# FiltreFSK_TI_LM386.net
KiCad netlist of a schematic drawn in EAGLE
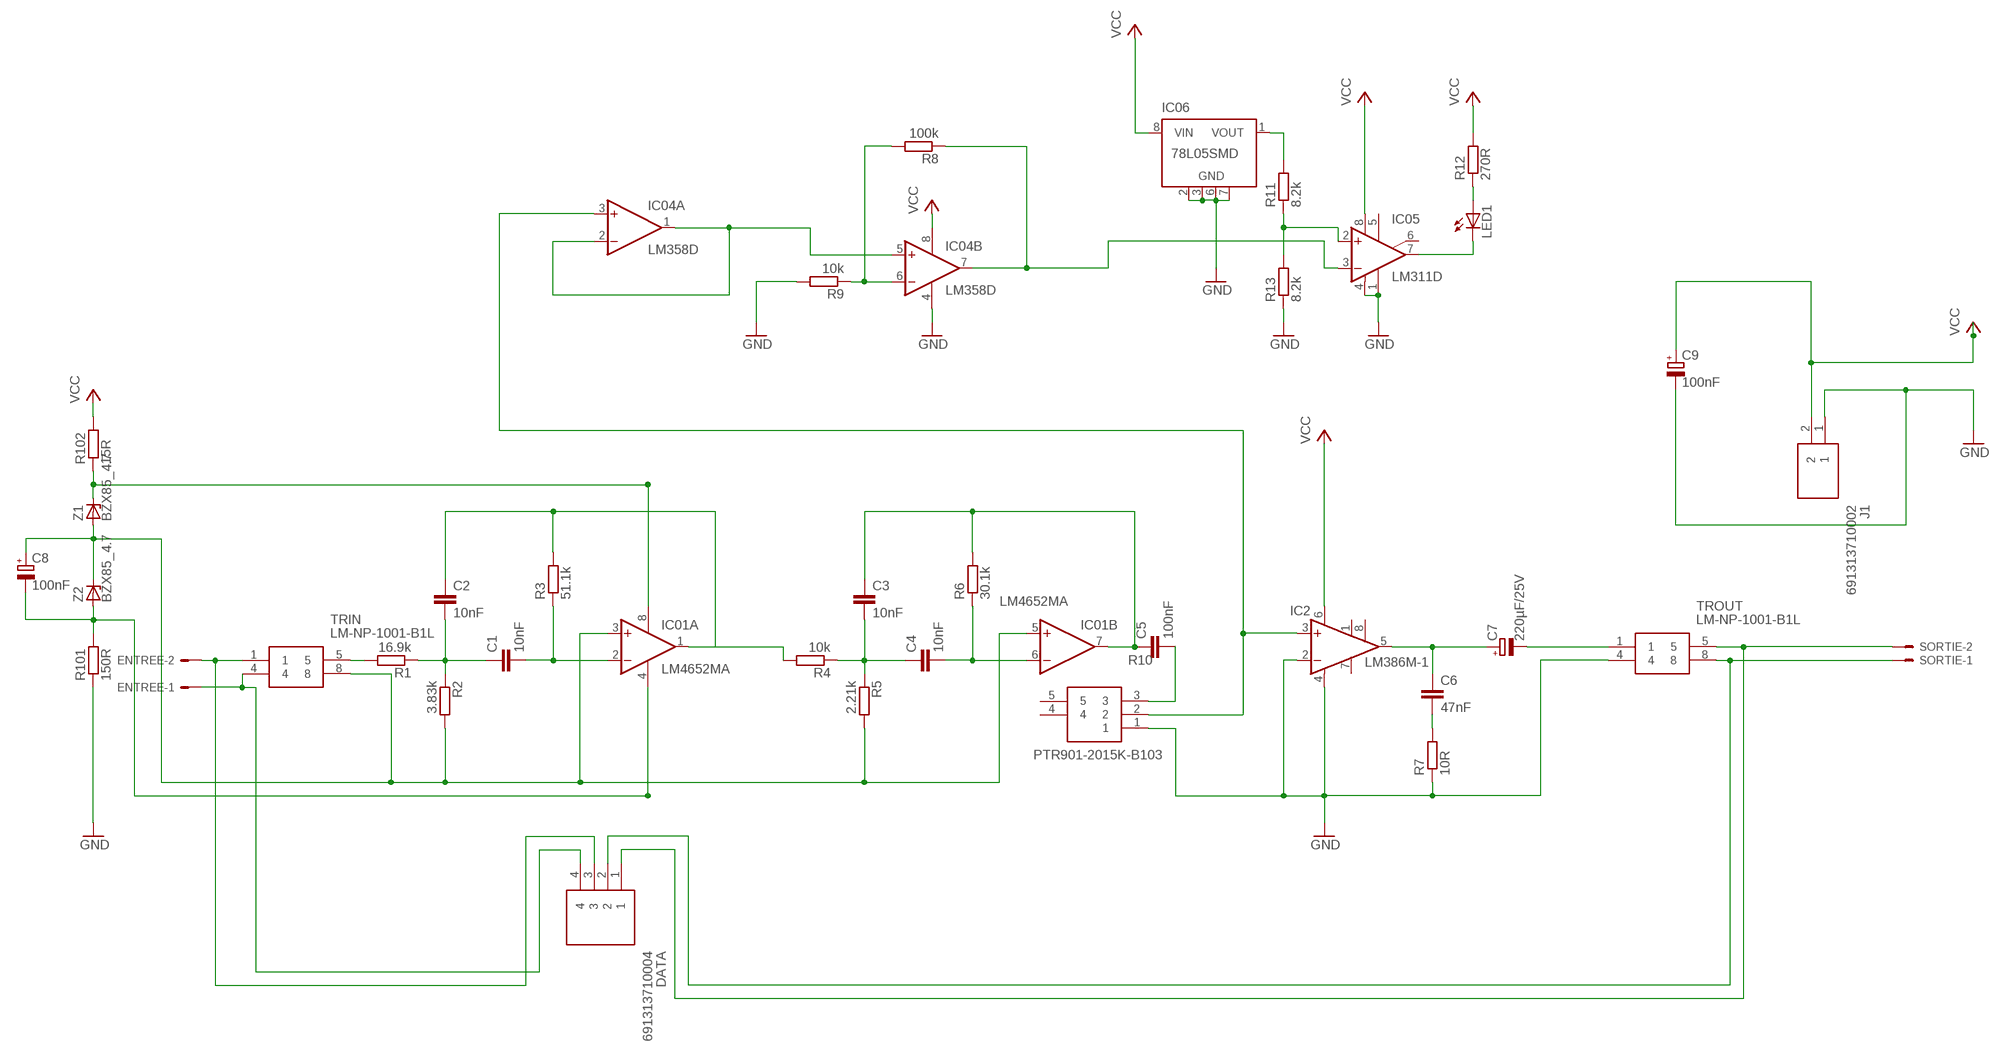
[diagram p0: schematic, sheet 1]

(export (version "E")
  (design (tool "Eeschema 10.0.6"))
  (components
    (comp (ref "C1")
      (value "10nF")
      (footprint "eagle-import:C1206")
      (libsource (lib "eagle-import") (part "C-EUC1206"))
    )
    (comp (ref "C2")
      (value "10nF")
      (footprint "eagle-import:C1206")
      (libsource (lib "eagle-import") (part "C-EUC1206"))
    )
    (comp (ref "C3")
      (value "10nF")
      (footprint "eagle-import:C1206")
      (libsource (lib "eagle-import") (part "C-EUC1206"))
    )
    (comp (ref "C4")
      (value "10nF")
      (footprint "eagle-import:C1206")
      (libsource (lib "eagle-import") (part "C-EUC1206"))
    )
    (comp (ref "C5")
      (value "100nF")
      (footprint "eagle-import:C1206")
      (libsource (lib "eagle-import") (part "C-EUC1206"))
    )
    (comp (ref "C6")
      (value "47nF")
      (footprint "eagle-import:C1206")
      (libsource (lib "eagle-import") (part "C-EUC1206"))
    )
    (comp (ref "C7")
      (value "220µF/25V")
      (footprint "eagle-import:E3,5-8")
      (libsource (lib "eagle-import") (part "CPOL-EUE3.5-8"))
    )
    (comp (ref "C8")
      (value "100nF")
      (footprint "eagle-import:E5-10,5")
      (libsource (lib "eagle-import") (part "CPOL-EUE5-10.5"))
    )
    (comp (ref "C9")
      (value "100nF")
      (footprint "eagle-import:E5-10,5")
      (libsource (lib "eagle-import") (part "CPOL-EUE5-10.5"))
    )
    (comp (ref "DATA")
      (value "691313710004")
      (footprint "eagle-import:SHDR4W140P0X500_1X4_2200X1200X")
      (fields
        (field (name "MOUSER_PART_NUMBER") "710-691313710004")
        (field (name "RS_PART_NUMBER") "8246576")
      )
      (libsource (lib "eagle-import") (part "691313710004"))
    )
    (comp (ref "ENTREE")
      (value "KK-156-2")
      (footprint "eagle-import:KK-156-2")
      (libsource (lib "eagle-import") (part "KK-156-2"))
    )
    (comp (ref "IC01")
      (value "LM4652MA")
      (footprint "eagle-import:SO08")
      (libsource (lib "eagle-import") (part "LM358D"))
    )
    (comp (ref "IC2")
      (value "LM386M-1")
      (footprint "eagle-import:SO08")
      (libsource (lib "eagle-import") (part "LM386?-M1"))
    )
    (comp (ref "IC04")
      (value "LM358D")
      (footprint "eagle-import:SO08")
      (libsource (lib "eagle-import") (part "LM358D"))
    )
    (comp (ref "IC05")
      (value "LM311D")
      (footprint "eagle-import:SO08")
      (libsource (lib "eagle-import") (part "LM311D"))
    )
    (comp (ref "IC06")
      (value "78L05SMD")
      (footprint "eagle-import:SO08")
      (libsource (lib "eagle-import") (part "78LSMD05"))
    )
    (comp (ref "J1")
      (value "691313710002")
      (footprint "eagle-import:691313710002")
      (fields (field (name "MOUSER_PART_NUMBER") "710-691313710002"))
      (libsource (lib "eagle-import") (part "691313710002"))
    )
    (comp (ref "LED1")
      (value "LED5MM")
      (footprint "eagle-import:LED5MM")
      (libsource (lib "eagle-import") (part "LED5MM"))
    )
    (comp (ref "R1")
      (value "16.9k")
      (footprint "eagle-import:R1206")
      (libsource (lib "eagle-import") (part "R-EU_R1206"))
    )
    (comp (ref "R2")
      (value "3.83k")
      (footprint "eagle-import:R1206")
      (libsource (lib "eagle-import") (part "R-EU_R1206"))
    )
    (comp (ref "R3")
      (value "51.1k")
      (footprint "eagle-import:R1206")
      (libsource (lib "eagle-import") (part "R-EU_R1206"))
    )
    (comp (ref "R4")
      (value "10k")
      (footprint "eagle-import:R1206")
      (libsource (lib "eagle-import") (part "R-EU_R1206"))
    )
    (comp (ref "R5")
      (value "2.21k")
      (footprint "eagle-import:R1206")
      (libsource (lib "eagle-import") (part "R-EU_R1206"))
    )
    (comp (ref "R6")
      (value "30.1k")
      (footprint "eagle-import:R1206")
      (libsource (lib "eagle-import") (part "R-EU_R1206"))
    )
    (comp (ref "R7")
      (value "10R")
      (footprint "eagle-import:R1206")
      (libsource (lib "eagle-import") (part "R-EU_R1206"))
    )
    (comp (ref "R8")
      (value "100k")
      (footprint "eagle-import:R1206")
      (libsource (lib "eagle-import") (part "R-EU_R1206"))
    )
    (comp (ref "R9")
      (value "10k")
      (footprint "eagle-import:R1206")
      (libsource (lib "eagle-import") (part "R-EU_R1206"))
    )
    (comp (ref "R10")
      (value "PTR901-2015K-B103")
      (footprint "eagle-import:PTR9012015KB103")
      (fields
        (field (name "MOUSER_PART_NUMBER") "652-PTR901-2015KB103")
        (field (name "RS_PART_NUMBER") "8275003P")
      )
      (libsource (lib "eagle-import") (part "PTR901-2015K-B103"))
    )
    (comp (ref "R11")
      (value "8.2k")
      (footprint "eagle-import:R1210")
      (libsource (lib "eagle-import") (part "R-EU_R1210"))
    )
    (comp (ref "R12")
      (value "270R")
      (footprint "eagle-import:R1206")
      (libsource (lib "eagle-import") (part "R-EU_R1206"))
    )
    (comp (ref "R13")
      (value "8.2k")
      (footprint "eagle-import:R1210")
      (libsource (lib "eagle-import") (part "R-EU_R1210"))
    )
    (comp (ref "R101")
      (value "150R")
      (footprint "eagle-import:0207_10")
      (libsource (lib "eagle-import") (part "R-EU_0207/10"))
    )
    (comp (ref "R102")
      (value "15R")
      (footprint "eagle-import:0207_10")
      (libsource (lib "eagle-import") (part "R-EU_0207/10"))
    )
    (comp (ref "SORTIE")
      (value "KK-156-2")
      (footprint "eagle-import:KK-156-2")
      (libsource (lib "eagle-import") (part "KK-156-2"))
    )
    (comp (ref "TRIN")
      (value "LM-NP-1001-B1L")
      (footprint "eagle-import:LMNP1001B1L")
      (fields
        (field (name "MOUSER_PART_NUMBER") "652-LM-NP-1001-B1L")
        (field (name "RS_PART_NUMBER") "1740620")
      )
      (libsource (lib "eagle-import") (part "LM-NP-1001-B1L"))
    )
    (comp (ref "TROUT")
      (value "LM-NP-1001-B1L")
      (footprint "eagle-import:LMNP1001B1L")
      (fields
        (field (name "MOUSER_PART_NUMBER") "652-LM-NP-1001-B1L")
        (field (name "RS_PART_NUMBER") "1740620")
      )
      (libsource (lib "eagle-import") (part "LM-NP-1001-B1L"))
    )
    (comp (ref "Z1")
      (value "BZX85_4.7")
      (footprint "eagle-import:DO41Z10")
      (libsource (lib "eagle-import") (part "BZX85"))
    )
    (comp (ref "Z2")
      (value "BZX85_4.7")
      (footprint "eagle-import:DO41Z10")
      (libsource (lib "eagle-import") (part "BZX85"))
    )
  )
  (nets
    (net (code "1") (name "GND") (class "Default")
      (node (ref "C9") (pin "-") (pinfunction "-_-") (pintype "passive"))
      (node (ref "IC04") (pin "4") (pinfunction "V-_4") (pintype "power_in"))
      (node (ref "IC05") (pin "1") (pinfunction "GND_1") (pintype "passive"))
      (node (ref "IC05") (pin "4") (pinfunction "V-_4") (pintype "power_in"))
      (node (ref "IC06") (pin "2") (pinfunction "GND_2") (pintype "power_in"))
      (node (ref "IC06") (pin "3") (pinfunction "GND_3") (pintype "power_in"))
      (node (ref "IC06") (pin "6") (pinfunction "GND_6") (pintype "power_in"))
      (node (ref "IC06") (pin "7") (pinfunction "GND_7") (pintype "power_in"))
      (node (ref "IC2") (pin "2") (pinfunction "-IN_2") (pintype "input"))
      (node (ref "IC2") (pin "4") (pinfunction "GND_4") (pintype "power_in"))
      (node (ref "J1") (pin "1") (pinfunction "1_1") (pintype "bidirectional"))
      (node (ref "R10") (pin "1") (pinfunction "1_1") (pintype "bidirectional"))
      (node (ref "R101") (pin "1") (pinfunction "1_1") (pintype "passive"))
      (node (ref "R13") (pin "1") (pinfunction "1_1") (pintype "passive"))
      (node (ref "R7") (pin "1") (pinfunction "1_1") (pintype "passive"))
      (node (ref "R9") (pin "2") (pinfunction "2_2") (pintype "passive"))
      (node (ref "TROUT") (pin "4") (pinfunction "4_4") (pintype "bidirectional"))
    )
    (net (code "2") (name "Net-(C1-Pad1)") (class "Default")
      (node (ref "C1") (pin "1") (pinfunction "1_1") (pintype "passive"))
      (node (ref "C2") (pin "2") (pinfunction "2_2") (pintype "passive"))
      (node (ref "R1") (pin "1") (pinfunction "1_1") (pintype "passive"))
      (node (ref "R2") (pin "1") (pinfunction "1_1") (pintype "passive"))
    )
    (net (code "3") (name "Net-(C3-Pad2)") (class "Default")
      (node (ref "C3") (pin "2") (pinfunction "2_2") (pintype "passive"))
      (node (ref "C4") (pin "1") (pinfunction "1_1") (pintype "passive"))
      (node (ref "R4") (pin "1") (pinfunction "1_1") (pintype "passive"))
      (node (ref "R5") (pin "1") (pinfunction "1_1") (pintype "passive"))
    )
    (net (code "4") (name "Net-(C5-Pad2)") (class "Default")
      (node (ref "C5") (pin "2") (pinfunction "2_2") (pintype "passive"))
      (node (ref "R10") (pin "3") (pinfunction "3_3") (pintype "bidirectional"))
    )
    (net (code "5") (name "Net-(C6-Pad2)") (class "Default")
      (node (ref "C6") (pin "2") (pinfunction "2_2") (pintype "passive"))
      (node (ref "R7") (pin "2") (pinfunction "2_2") (pintype "passive"))
    )
    (net (code "6") (name "Net-(C7-Pad-)") (class "Default")
      (node (ref "C7") (pin "-") (pinfunction "-_-") (pintype "passive"))
      (node (ref "TROUT") (pin "1") (pinfunction "1_1") (pintype "bidirectional"))
    )
    (net (code "7") (name "Net-(ENTREEA-S)") (class "Default")
      (node (ref "DATA") (pin "4") (pinfunction "4_4") (pintype "bidirectional"))
      (node (ref "ENTREE") (pin "1") (pinfunction "S_1") (pintype "passive"))
      (node (ref "TRIN") (pin "4") (pinfunction "4_4") (pintype "bidirectional"))
    )
    (net (code "8") (name "Net-(ENTREEB-S)") (class "Default")
      (node (ref "DATA") (pin "3") (pinfunction "3_3") (pintype "bidirectional"))
      (node (ref "ENTREE") (pin "2") (pinfunction "S_2") (pintype "passive"))
      (node (ref "TRIN") (pin "1") (pinfunction "1_1") (pintype "bidirectional"))
    )
    (net (code "9") (name "Net-(IC01A-+IN)") (class "Default")
      (node (ref "C8") (pin "+") (pinfunction "+_+") (pintype "passive"))
      (node (ref "IC01") (pin "3") (pinfunction "+IN_3") (pintype "input"))
      (node (ref "IC01") (pin "5") (pinfunction "+IN_5") (pintype "input"))
      (node (ref "R2") (pin "2") (pinfunction "2_2") (pintype "passive"))
      (node (ref "R5") (pin "2") (pinfunction "2_2") (pintype "passive"))
      (node (ref "TRIN") (pin "8") (pinfunction "8_8") (pintype "bidirectional"))
      (node (ref "Z1") (pin "A") (pinfunction "A_A") (pintype "passive"))
      (node (ref "Z2") (pin "C") (pinfunction "C_C") (pintype "passive"))
    )
    (net (code "10") (name "Net-(IC01A--IN)") (class "Default")
      (node (ref "C1") (pin "2") (pinfunction "2_2") (pintype "passive"))
      (node (ref "IC01") (pin "2") (pinfunction "-IN_2") (pintype "input"))
      (node (ref "R3") (pin "1") (pinfunction "1_1") (pintype "passive"))
    )
    (net (code "11") (name "Net-(IC01A-OUT)") (class "Default")
      (node (ref "C2") (pin "1") (pinfunction "1_1") (pintype "passive"))
      (node (ref "IC01") (pin "1") (pinfunction "OUT_1") (pintype "output"))
      (node (ref "R3") (pin "2") (pinfunction "2_2") (pintype "passive"))
      (node (ref "R4") (pin "2") (pinfunction "2_2") (pintype "passive"))
    )
    (net (code "12") (name "Net-(IC01B--IN)") (class "Default")
      (node (ref "C4") (pin "2") (pinfunction "2_2") (pintype "passive"))
      (node (ref "IC01") (pin "6") (pinfunction "-IN_6") (pintype "input"))
      (node (ref "R6") (pin "1") (pinfunction "1_1") (pintype "passive"))
    )
    (net (code "13") (name "Net-(IC01B-OUT)") (class "Default")
      (node (ref "C3") (pin "1") (pinfunction "1_1") (pintype "passive"))
      (node (ref "C5") (pin "1") (pinfunction "1_1") (pintype "passive"))
      (node (ref "IC01") (pin "7") (pinfunction "OUT_7") (pintype "output"))
      (node (ref "R6") (pin "2") (pinfunction "2_2") (pintype "passive"))
    )
    (net (code "14") (name "Net-(IC01C-V+)") (class "Default")
      (node (ref "IC01") (pin "8") (pinfunction "V+_8") (pintype "power_in"))
      (node (ref "R102") (pin "1") (pinfunction "1_1") (pintype "passive"))
      (node (ref "Z1") (pin "C") (pinfunction "C_C") (pintype "passive"))
    )
    (net (code "15") (name "Net-(IC01C-V-)") (class "Default")
      (node (ref "C8") (pin "-") (pinfunction "-_-") (pintype "passive"))
      (node (ref "IC01") (pin "4") (pinfunction "V-_4") (pintype "power_in"))
      (node (ref "R101") (pin "2") (pinfunction "2_2") (pintype "passive"))
      (node (ref "Z2") (pin "A") (pinfunction "A_A") (pintype "passive"))
    )
    (net (code "16") (name "Net-(IC2-OUT)") (class "Default")
      (node (ref "C6") (pin "1") (pinfunction "1_1") (pintype "passive"))
      (node (ref "C7") (pin "+") (pinfunction "+_+") (pintype "passive"))
      (node (ref "IC2") (pin "5") (pinfunction "OUT_5") (pintype "output"))
    )
    (net (code "17") (name "Net-(IC04A-+IN)") (class "Default")
      (node (ref "IC04") (pin "3") (pinfunction "+IN_3") (pintype "input"))
      (node (ref "IC2") (pin "3") (pinfunction "+IN_3") (pintype "input"))
      (node (ref "R10") (pin "2") (pinfunction "2_2") (pintype "bidirectional"))
    )
    (net (code "18") (name "Net-(IC04A--IN)") (class "Default")
      (node (ref "IC04") (pin "1") (pinfunction "OUT_1") (pintype "output"))
      (node (ref "IC04") (pin "2") (pinfunction "-IN_2") (pintype "input"))
      (node (ref "IC04") (pin "5") (pinfunction "+IN_5") (pintype "input"))
    )
    (net (code "19") (name "Net-(IC04B--IN)") (class "Default")
      (node (ref "IC04") (pin "6") (pinfunction "-IN_6") (pintype "input"))
      (node (ref "R8") (pin "2") (pinfunction "2_2") (pintype "passive"))
      (node (ref "R9") (pin "1") (pinfunction "1_1") (pintype "passive"))
    )
    (net (code "20") (name "Net-(IC04B-OUT)") (class "Default")
      (node (ref "IC04") (pin "7") (pinfunction "OUT_7") (pintype "output"))
      (node (ref "IC05") (pin "3") (pinfunction "-IN_3") (pintype "input"))
      (node (ref "R8") (pin "1") (pinfunction "1_1") (pintype "passive"))
    )
    (net (code "21") (name "Net-(IC05-+IN)") (class "Default")
      (node (ref "IC05") (pin "2") (pinfunction "+IN_2") (pintype "input"))
      (node (ref "R11") (pin "1") (pinfunction "1_1") (pintype "passive"))
      (node (ref "R13") (pin "2") (pinfunction "2_2") (pintype "passive"))
    )
    (net (code "22") (name "Net-(IC05-OUT)") (class "Default")
      (node (ref "IC05") (pin "7") (pinfunction "OUT_7") (pintype "output"))
      (node (ref "LED1") (pin "K") (pinfunction "C_K") (pintype "passive"))
    )
    (net (code "23") (name "Net-(IC06A-VOUT)") (class "Default")
      (node (ref "IC06") (pin "1") (pinfunction "VOUT_1") (pintype "output"))
      (node (ref "R11") (pin "2") (pinfunction "2_2") (pintype "passive"))
    )
    (net (code "24") (name "Net-(LED1-PadA)") (class "Default")
      (node (ref "LED1") (pin "A") (pinfunction "A_A") (pintype "passive"))
      (node (ref "R12") (pin "1") (pinfunction "1_1") (pintype "passive"))
    )
    (net (code "25") (name "Net-(R1-Pad2)") (class "Default")
      (node (ref "R1") (pin "2") (pinfunction "2_2") (pintype "passive"))
      (node (ref "TRIN") (pin "5") (pinfunction "5_5") (pintype "bidirectional"))
    )
    (net (code "26") (name "Net-(SORTIEA-S)") (class "Default")
      (node (ref "DATA") (pin "2") (pinfunction "2_2") (pintype "bidirectional"))
      (node (ref "SORTIE") (pin "1") (pinfunction "S_1") (pintype "passive"))
      (node (ref "TROUT") (pin "8") (pinfunction "8_8") (pintype "bidirectional"))
    )
    (net (code "27") (name "Net-(SORTIEB-S)") (class "Default")
      (node (ref "DATA") (pin "1") (pinfunction "1_1") (pintype "bidirectional"))
      (node (ref "SORTIE") (pin "2") (pinfunction "S_2") (pintype "passive"))
      (node (ref "TROUT") (pin "5") (pinfunction "5_5") (pintype "bidirectional"))
    )
    (net (code "28") (name "VCC") (class "Default")
      (node (ref "C9") (pin "+") (pinfunction "+_+") (pintype "passive"))
      (node (ref "IC04") (pin "8") (pinfunction "V+_8") (pintype "power_in"))
      (node (ref "IC05") (pin "8") (pinfunction "V+_8") (pintype "power_in"))
      (node (ref "IC06") (pin "8") (pinfunction "VIN_8") (pintype "passive"))
      (node (ref "IC2") (pin "6") (pinfunction "VS_6") (pintype "power_in"))
      (node (ref "J1") (pin "2") (pinfunction "2_2") (pintype "bidirectional"))
      (node (ref "R102") (pin "2") (pinfunction "2_2") (pintype "passive"))
      (node (ref "R12") (pin "2") (pinfunction "2_2") (pintype "passive"))
    )
    (net (code "29") (name "unconnected-(IC2-BYPASS-Pad7)") (class "Default")
      (node (ref "IC2") (pin "7") (pinfunction "BYPASS_7") (pintype "passive"))
    )
    (net (code "30") (name "unconnected-(IC2-GAIN-Pad1)") (class "Default")
      (node (ref "IC2") (pin "1") (pinfunction "GAIN_1") (pintype "passive"))
    )
    (net (code "31") (name "unconnected-(IC2-GAIN-Pad8)") (class "Default")
      (node (ref "IC2") (pin "8") (pinfunction "GAIN_8") (pintype "passive"))
    )
    (net (code "32") (name "unconnected-(IC05-ON-Pad5)") (class "Default")
      (node (ref "IC05") (pin "5") (pinfunction "ON_5") (pintype "passive"))
    )
    (net (code "33") (name "unconnected-(IC05-ON{slash}STR-Pad6)") (class "Default")
      (node (ref "IC05") (pin "6") (pinfunction "ON/STR_6") (pintype "passive"))
    )
    (net (code "34") (name "unconnected-(R10-Pad4)") (class "Default")
      (node (ref "R10") (pin "4") (pinfunction "4_4") (pintype "bidirectional"))
    )
    (net (code "35") (name "unconnected-(R10-Pad5)") (class "Default")
      (node (ref "R10") (pin "5") (pinfunction "5_5") (pintype "bidirectional"))
    )
  )
)
